# ZED-F9P_GNSS_FeatherWing.net
KiCad netlist of a schematic drawn in EAGLE
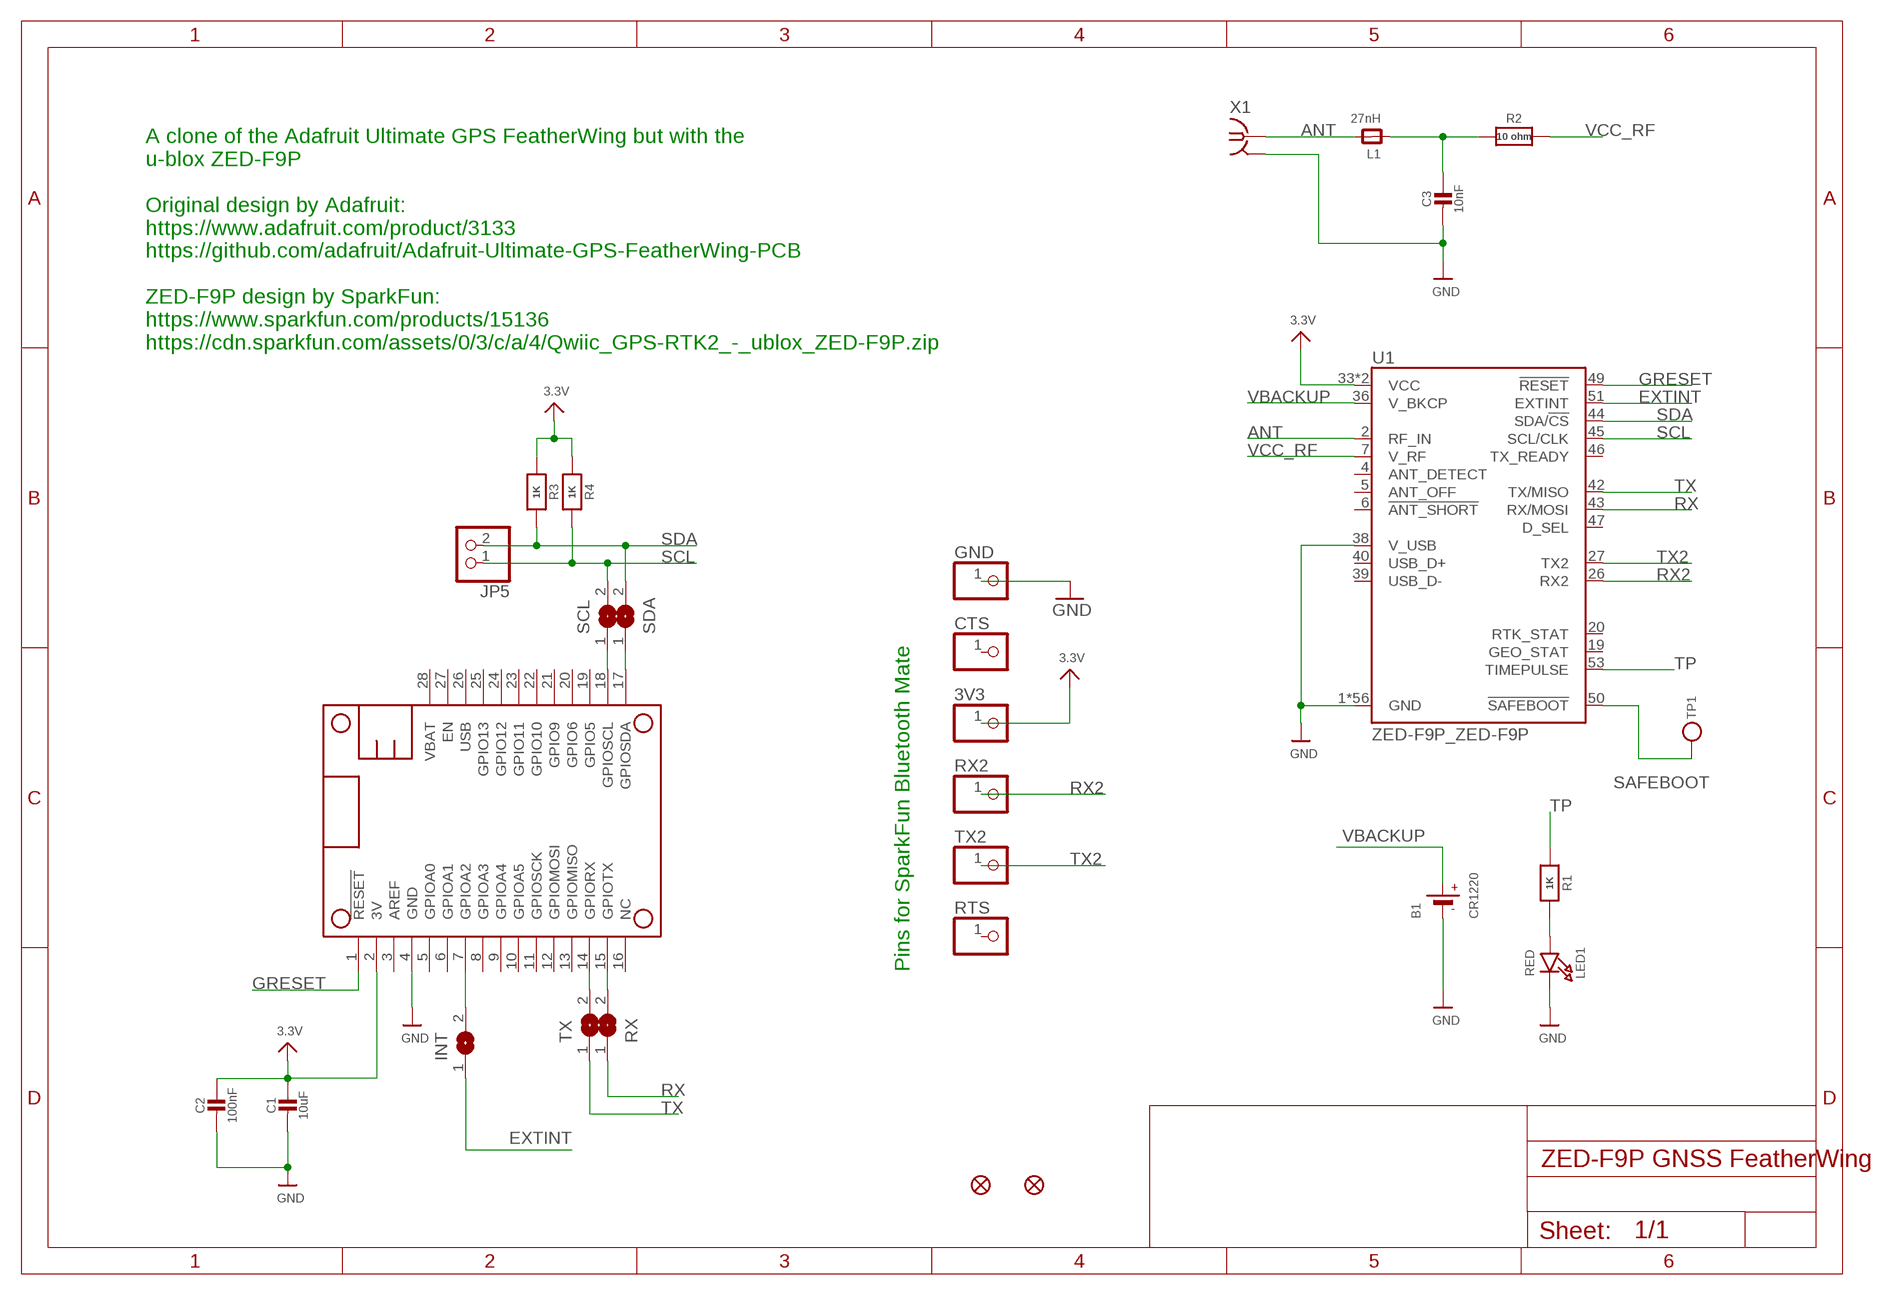
[diagram p0: schematic, sheet 1]

(export (version "E")
  (design (tool "Eeschema 10.0.6"))
  (components
    (comp (ref "3V3")
      (value "PINHD-1X1")
      (footprint "eagle-import:1X01")
      (libsource (lib "eagle-import") (part "PINHD-1X1"))
    )
    (comp (ref "B1")
      (value "CR1220")
      (footprint "eagle-import:CR1220-2")
      (libsource (lib "eagle-import") (part "BATTERYCR1220_2"))
    )
    (comp (ref "C1")
      (value "10uF")
      (footprint "eagle-import:0805-NO")
      (libsource (lib "eagle-import") (part "CAP_CERAMIC0805-NOOUTLINE"))
    )
    (comp (ref "C2")
      (value "100nF")
      (footprint "eagle-import:0805-NO")
      (libsource (lib "eagle-import") (part "CAP_CERAMIC0805-NOOUTLINE"))
    )
    (comp (ref "C3")
      (value "10nF")
      (footprint "eagle-import:0805-NO")
      (libsource (lib "eagle-import") (part "CAP_CERAMIC0805-NOOUTLINE"))
    )
    (comp (ref "CTS")
      (value "PINHD-1X1")
      (footprint "eagle-import:1X01")
      (libsource (lib "eagle-import") (part "PINHD-1X1"))
    )
    (comp (ref "FID1")
      (value "FIDUCIAL\"\"")
      (footprint "eagle-import:FIDUCIAL_1MM")
      (libsource (lib "eagle-import") (part "FIDUCIAL{dblquote}{dblquote}"))
    )
    (comp (ref "FID2")
      (value "FIDUCIAL\"\"")
      (footprint "eagle-import:FIDUCIAL_1MM")
      (libsource (lib "eagle-import") (part "FIDUCIAL{dblquote}{dblquote}"))
    )
    (comp (ref "GND")
      (value "PINHD-1X1")
      (footprint "eagle-import:1X01")
      (libsource (lib "eagle-import") (part "PINHD-1X1"))
    )
    (comp (ref "INT")
      (value "SOLDERJUMPERCLOSED")
      (footprint "eagle-import:SOLDERJUMPER_CLOSEDWIRE")
      (libsource (lib "eagle-import") (part "SOLDERJUMPERCLOSED"))
    )
    (comp (ref "JP5")
      (value "HEADER-1X2ROUND")
      (footprint "eagle-import:1X02_ROUND")
      (libsource (lib "eagle-import") (part "HEADER-1X2ROUND"))
    )
    (comp (ref "L1")
      (value "27nH")
      (footprint "eagle-import:0805-NO")
      (libsource (lib "eagle-import") (part "FERRITE-0805NO"))
    )
    (comp (ref "LED1")
      (value "RED")
      (footprint "eagle-import:CHIPLED_0805_NOOUTLINE")
      (libsource (lib "eagle-import") (part "LED0805_NOOUTLINE"))
    )
    (comp (ref "MS1")
      (value "MICROBUILDER_FEATHERWINGMICROBUILDER_FEATHERWING_HOLES")
      (footprint "eagle-import:MICROBUILDER_FEATHERWING_HOLES")
      (libsource (lib "eagle-import") (part "MICROBUILDER_FEATHERWINGMICROBUILDER_FEATHERWING_HOLES"))
    )
    (comp (ref "R1")
      (value "1K")
      (footprint "eagle-import:0603-NO")
      (libsource (lib "eagle-import") (part "RESISTOR_0603_NOOUT"))
    )
    (comp (ref "R2")
      (value "10 ohm")
      (footprint "eagle-import:0805-NO")
      (libsource (lib "eagle-import") (part "RESISTOR0805_NOOUTLINE"))
    )
    (comp (ref "R3")
      (value "1K")
      (footprint "eagle-import:0603-NO")
      (libsource (lib "eagle-import") (part "RESISTOR_0603_NOOUT"))
    )
    (comp (ref "R4")
      (value "1K")
      (footprint "eagle-import:0603-NO")
      (libsource (lib "eagle-import") (part "RESISTOR_0603_NOOUT"))
    )
    (comp (ref "RTS")
      (value "PINHD-1X1")
      (footprint "eagle-import:1X01")
      (libsource (lib "eagle-import") (part "PINHD-1X1"))
    )
    (comp (ref "RX")
      (value "SOLDERJUMPERCLOSED")
      (footprint "eagle-import:SOLDERJUMPER_CLOSEDWIRE")
      (libsource (lib "eagle-import") (part "SOLDERJUMPERCLOSED"))
    )
    (comp (ref "RX2")
      (value "PINHD-1X1")
      (footprint "eagle-import:1X01")
      (libsource (lib "eagle-import") (part "PINHD-1X1"))
    )
    (comp (ref "SCL")
      (value "SOLDERJUMPERCLOSED")
      (footprint "eagle-import:SOLDERJUMPER_CLOSEDWIRE")
      (libsource (lib "eagle-import") (part "SOLDERJUMPERCLOSED"))
    )
    (comp (ref "SDA")
      (value "SOLDERJUMPERCLOSED")
      (footprint "eagle-import:SOLDERJUMPER_CLOSEDWIRE")
      (libsource (lib "eagle-import") (part "SOLDERJUMPERCLOSED"))
    )
    (comp (ref "TP1")
      (value "TESTPOINTROUND1.5MM")
      (footprint "eagle-import:TESTPOINT_ROUND_1.5MM")
      (libsource (lib "eagle-import") (part "TESTPOINTROUND1.5MM"))
    )
    (comp (ref "TX")
      (value "SOLDERJUMPERCLOSED")
      (footprint "eagle-import:SOLDERJUMPER_CLOSEDWIRE")
      (libsource (lib "eagle-import") (part "SOLDERJUMPERCLOSED"))
    )
    (comp (ref "TX2")
      (value "PINHD-1X1")
      (footprint "eagle-import:1X01")
      (libsource (lib "eagle-import") (part "PINHD-1X1"))
    )
    (comp (ref "U1")
      (value "ZED-F9P_ZED-F9P")
      (footprint "eagle-import:ZED-F9P_ZED-F9P")
      (libsource (lib "eagle-import") (part "ZED-F9P_ZED-F9P"))
    )
    (comp (ref "X1")
      (value "SMA-142-0711-821/826")
      (footprint "eagle-import:J502-ND-142-0711-821_826")
      (fields (field (name "MF") "JOHNSON COMPONENTS") (field (name "MPN") "142-0711-821"))
      (libsource (lib "eagle-import") (part "SMA-142-0711-821/826"))
    )
  )
  (nets
    (net (code "1") (name "/ANT") (class "Default")
      (node (ref "L1") (pin "2") (pinfunction "P$2_2") (pintype "passive"))
      (node (ref "U1") (pin "2") (pinfunction "RF_IN_2") (pintype "bidirectional"))
      (node (ref "X1") (pin "1") (pinfunction "1_1") (pintype "passive"))
    )
    (net (code "2") (name "/EXTINT") (class "Default")
      (node (ref "INT") (pin "1") (pinfunction "1_1") (pintype "passive"))
      (node (ref "U1") (pin "51") (pinfunction "EXTINT_51") (pintype "bidirectional"))
    )
    (net (code "3") (name "/GRESET") (class "Default")
      (node (ref "MS1") (pin "1") (pinfunction "~{RESET}_1") (pintype "input"))
      (node (ref "U1") (pin "49") (pinfunction "~{RESET}_49") (pintype "bidirectional"))
    )
    (net (code "4") (name "/RX") (class "Default")
      (node (ref "RX") (pin "1") (pinfunction "1_1") (pintype "passive"))
      (node (ref "U1") (pin "43") (pinfunction "RX/MOSI_43") (pintype "bidirectional"))
    )
    (net (code "5") (name "/RX2") (class "Default")
      (node (ref "RX2") (pin "1") (pinfunction "1_1") (pintype "passive"))
      (node (ref "U1") (pin "26") (pinfunction "RX2_26") (pintype "bidirectional"))
    )
    (net (code "6") (name "/SAFEBOOT") (class "Default")
      (node (ref "TP1") (pin "P$1") (pinfunction "P$1_P$1") (pintype "bidirectional"))
      (node (ref "U1") (pin "50") (pinfunction "~{SAFEBOOT}_50") (pintype "bidirectional"))
    )
    (net (code "7") (name "/SCL") (class "Default")
      (node (ref "JP5") (pin "1") (pinfunction "1_1") (pintype "passive"))
      (node (ref "R4") (pin "2") (pinfunction "2_2") (pintype "passive"))
      (node (ref "SCL") (pin "2") (pinfunction "2_2") (pintype "passive"))
      (node (ref "U1") (pin "45") (pinfunction "SCL/CLK_45") (pintype "bidirectional"))
    )
    (net (code "8") (name "/SDA") (class "Default")
      (node (ref "JP5") (pin "2") (pinfunction "2_2") (pintype "passive"))
      (node (ref "R3") (pin "2") (pinfunction "2_2") (pintype "passive"))
      (node (ref "SDA") (pin "2") (pinfunction "2_2") (pintype "passive"))
      (node (ref "U1") (pin "44") (pinfunction "SDA/~{CS}_44") (pintype "bidirectional"))
    )
    (net (code "9") (name "/TP") (class "Default")
      (node (ref "R1") (pin "1") (pinfunction "1_1") (pintype "passive"))
      (node (ref "U1") (pin "53") (pinfunction "TIMEPULSE_53") (pintype "bidirectional"))
    )
    (net (code "10") (name "/TX") (class "Default")
      (node (ref "TX") (pin "1") (pinfunction "1_1") (pintype "passive"))
      (node (ref "U1") (pin "42") (pinfunction "TX/MISO_42") (pintype "bidirectional"))
    )
    (net (code "11") (name "/TX2") (class "Default")
      (node (ref "TX2") (pin "1") (pinfunction "1_1") (pintype "passive"))
      (node (ref "U1") (pin "27") (pinfunction "TX2_27") (pintype "bidirectional"))
    )
    (net (code "12") (name "/USB") (class "Default")
      (node (ref "MS1") (pin "26") (pinfunction "USB_26") (pintype "power_in"))
    )
    (net (code "13") (name "/VBACKUP") (class "Default")
      (node (ref "B1") (pin "+") (pinfunction "+_+") (pintype "passive"))
      (node (ref "U1") (pin "36") (pinfunction "V_BKCP_36") (pintype "bidirectional"))
    )
    (net (code "14") (name "/VBAT") (class "Default")
      (node (ref "MS1") (pin "28") (pinfunction "VBAT_28") (pintype "power_in"))
    )
    (net (code "15") (name "/VCC_RF") (class "Default")
      (node (ref "R2") (pin "2") (pinfunction "2_2") (pintype "passive"))
      (node (ref "U1") (pin "7") (pinfunction "V_RF_7") (pintype "bidirectional"))
    )
    (net (code "16") (name "3.3V") (class "Default")
      (node (ref "3V3") (pin "1") (pinfunction "1_1") (pintype "passive"))
      (node (ref "C1") (pin "1") (pinfunction "1_1") (pintype "passive"))
      (node (ref "C2") (pin "1") (pinfunction "1_1") (pintype "passive"))
      (node (ref "MS1") (pin "2") (pinfunction "3V_2") (pintype "power_in"))
      (node (ref "R3") (pin "1") (pinfunction "1_1") (pintype "passive"))
      (node (ref "R4") (pin "1") (pinfunction "1_1") (pintype "passive"))
      (node (ref "U1") (pin "33") (pinfunction "VCC_33") (pintype "bidirectional"))
      (node (ref "U1") (pin "34") (pinfunction "VCC_34") (pintype "bidirectional"))
    )
    (net (code "17") (name "GND") (class "Default")
      (node (ref "B1") (pin "-") (pinfunction "-_-") (pintype "passive"))
      (node (ref "C1") (pin "2") (pinfunction "2_2") (pintype "passive"))
      (node (ref "C2") (pin "2") (pinfunction "2_2") (pintype "passive"))
      (node (ref "C3") (pin "2") (pinfunction "2_2") (pintype "passive"))
      (node (ref "GND") (pin "1") (pinfunction "1_1") (pintype "passive"))
      (node (ref "LED1") (pin "C") (pinfunction "C_C") (pintype "passive"))
      (node (ref "MS1") (pin "4") (pinfunction "GND_4") (pintype "power_in"))
      (node (ref "U1") (pin "1") (pinfunction "GND_1") (pintype "bidirectional"))
      (node (ref "U1") (pin "100") (pinfunction "GND_100") (pintype "bidirectional"))
      (node (ref "U1") (pin "101") (pinfunction "GND_101") (pintype "bidirectional"))
      (node (ref "U1") (pin "102") (pinfunction "GND_102") (pintype "bidirectional"))
      (node (ref "U1") (pin "12") (pinfunction "GND_12") (pintype "bidirectional"))
      (node (ref "U1") (pin "14") (pinfunction "GND_14") (pintype "bidirectional"))
      (node (ref "U1") (pin "3") (pinfunction "GND_3") (pintype "bidirectional"))
      (node (ref "U1") (pin "32") (pinfunction "GND_32") (pintype "bidirectional"))
      (node (ref "U1") (pin "37") (pinfunction "GND_37") (pintype "bidirectional"))
      (node (ref "U1") (pin "38") (pinfunction "V_USB_38") (pintype "bidirectional"))
      (node (ref "U1") (pin "41") (pinfunction "GND_41") (pintype "bidirectional"))
      (node (ref "U1") (pin "48") (pinfunction "GND_48") (pintype "bidirectional"))
      (node (ref "U1") (pin "55") (pinfunction "GND_55") (pintype "bidirectional"))
      (node (ref "U1") (pin "56") (pinfunction "GND_56") (pintype "bidirectional"))
      (node (ref "U1") (pin "57") (pinfunction "GND_57") (pintype "bidirectional"))
      (node (ref "U1") (pin "58") (pinfunction "GND_58") (pintype "bidirectional"))
      (node (ref "U1") (pin "59") (pinfunction "GND_59") (pintype "bidirectional"))
      (node (ref "U1") (pin "60") (pinfunction "GND_60") (pintype "bidirectional"))
      (node (ref "U1") (pin "61") (pinfunction "GND_61") (pintype "bidirectional"))
      (node (ref "U1") (pin "62") (pinfunction "GND_62") (pintype "bidirectional"))
      (node (ref "U1") (pin "63") (pinfunction "GND_63") (pintype "bidirectional"))
      (node (ref "U1") (pin "64") (pinfunction "GND_64") (pintype "bidirectional"))
      (node (ref "U1") (pin "65") (pinfunction "GND_65") (pintype "bidirectional"))
      (node (ref "U1") (pin "66") (pinfunction "GND_66") (pintype "bidirectional"))
      (node (ref "U1") (pin "67") (pinfunction "GND_67") (pintype "bidirectional"))
      (node (ref "U1") (pin "68") (pinfunction "GND_68") (pintype "bidirectional"))
      (node (ref "U1") (pin "69") (pinfunction "GND_69") (pintype "bidirectional"))
      (node (ref "U1") (pin "70") (pinfunction "GND_70") (pintype "bidirectional"))
      (node (ref "U1") (pin "71") (pinfunction "GND_71") (pintype "bidirectional"))
      (node (ref "U1") (pin "72") (pinfunction "GND_72") (pintype "bidirectional"))
      (node (ref "U1") (pin "73") (pinfunction "GND_73") (pintype "bidirectional"))
      (node (ref "U1") (pin "74") (pinfunction "GND_74") (pintype "bidirectional"))
      (node (ref "U1") (pin "75") (pinfunction "GND_75") (pintype "bidirectional"))
      (node (ref "U1") (pin "76") (pinfunction "GND_76") (pintype "bidirectional"))
      (node (ref "U1") (pin "77") (pinfunction "GND_77") (pintype "bidirectional"))
      (node (ref "U1") (pin "78") (pinfunction "GND_78") (pintype "bidirectional"))
      (node (ref "U1") (pin "79") (pinfunction "GND_79") (pintype "bidirectional"))
      (node (ref "U1") (pin "80") (pinfunction "GND_80") (pintype "bidirectional"))
      (node (ref "U1") (pin "81") (pinfunction "GND_81") (pintype "bidirectional"))
      (node (ref "U1") (pin "82") (pinfunction "GND_82") (pintype "bidirectional"))
      (node (ref "U1") (pin "83") (pinfunction "GND_83") (pintype "bidirectional"))
      (node (ref "U1") (pin "84") (pinfunction "GND_84") (pintype "bidirectional"))
      (node (ref "U1") (pin "85") (pinfunction "GND_85") (pintype "bidirectional"))
      (node (ref "U1") (pin "86") (pinfunction "GND_86") (pintype "bidirectional"))
      (node (ref "U1") (pin "87") (pinfunction "GND_87") (pintype "bidirectional"))
      (node (ref "U1") (pin "88") (pinfunction "GND_88") (pintype "bidirectional"))
      (node (ref "U1") (pin "89") (pinfunction "GND_89") (pintype "bidirectional"))
      (node (ref "U1") (pin "90") (pinfunction "GND_90") (pintype "bidirectional"))
      (node (ref "U1") (pin "91") (pinfunction "GND_91") (pintype "bidirectional"))
      (node (ref "U1") (pin "92") (pinfunction "GND_92") (pintype "bidirectional"))
      (node (ref "U1") (pin "93") (pinfunction "GND_93") (pintype "bidirectional"))
      (node (ref "U1") (pin "94") (pinfunction "GND_94") (pintype "bidirectional"))
      (node (ref "U1") (pin "95") (pinfunction "GND_95") (pintype "bidirectional"))
      (node (ref "U1") (pin "96") (pinfunction "GND_96") (pintype "bidirectional"))
      (node (ref "U1") (pin "97") (pinfunction "GND_97") (pintype "bidirectional"))
      (node (ref "U1") (pin "98") (pinfunction "GND_98") (pintype "bidirectional"))
      (node (ref "U1") (pin "99") (pinfunction "GND_99") (pintype "bidirectional"))
      (node (ref "X1") (pin "G@1") (pinfunction "2_G@1") (pintype "passive"))
      (node (ref "X1") (pin "G@2") (pinfunction "2_G@2") (pintype "passive"))
      (node (ref "X1") (pin "G@3") (pinfunction "2_G@3") (pintype "passive"))
      (node (ref "X1") (pin "G@4") (pinfunction "2_G@4") (pintype "passive"))
    )
    (net (code "18") (name "Net-(L1-P$1)") (class "Default")
      (node (ref "C3") (pin "1") (pinfunction "1_1") (pintype "passive"))
      (node (ref "L1") (pin "1") (pinfunction "P$1_1") (pintype "passive"))
      (node (ref "R2") (pin "1") (pinfunction "1_1") (pintype "passive"))
    )
    (net (code "19") (name "Net-(LED1-PadA)") (class "Default")
      (node (ref "LED1") (pin "A") (pinfunction "A_A") (pintype "passive"))
      (node (ref "R1") (pin "2") (pinfunction "2_2") (pintype "passive"))
    )
    (net (code "20") (name "Net-(MS1-GPIOA2)") (class "Default")
      (node (ref "INT") (pin "2") (pinfunction "2_2") (pintype "passive"))
      (node (ref "MS1") (pin "7") (pinfunction "GPIOA2_7") (pintype "bidirectional"))
    )
    (net (code "21") (name "Net-(MS1-GPIORX)") (class "Default")
      (node (ref "MS1") (pin "14") (pinfunction "GPIORX_14") (pintype "bidirectional"))
      (node (ref "TX") (pin "2") (pinfunction "2_2") (pintype "passive"))
    )
    (net (code "22") (name "Net-(MS1-GPIOSCL)") (class "Default")
      (node (ref "MS1") (pin "18") (pinfunction "GPIOSCL_18") (pintype "bidirectional"))
      (node (ref "SCL") (pin "1") (pinfunction "1_1") (pintype "passive"))
    )
    (net (code "23") (name "Net-(MS1-GPIOSDA)") (class "Default")
      (node (ref "MS1") (pin "17") (pinfunction "GPIOSDA_17") (pintype "bidirectional"))
      (node (ref "SDA") (pin "1") (pinfunction "1_1") (pintype "passive"))
    )
    (net (code "24") (name "Net-(MS1-GPIOTX)") (class "Default")
      (node (ref "MS1") (pin "15") (pinfunction "GPIOTX_15") (pintype "bidirectional"))
      (node (ref "RX") (pin "2") (pinfunction "2_2") (pintype "passive"))
    )
    (net (code "25") (name "unconnected-(CTS-Pad1)") (class "Default")
      (node (ref "CTS") (pin "1") (pinfunction "1_1") (pintype "passive"))
    )
    (net (code "26") (name "unconnected-(MS1-AREF-Pad3)") (class "Default")
      (node (ref "MS1") (pin "3") (pinfunction "AREF_3") (pintype "passive"))
    )
    (net (code "27") (name "unconnected-(MS1-EN-Pad27)") (class "Default")
      (node (ref "MS1") (pin "27") (pinfunction "EN_27") (pintype "passive"))
    )
    (net (code "28") (name "unconnected-(MS1-GPIO5-Pad19)") (class "Default")
      (node (ref "MS1") (pin "19") (pinfunction "GPIO5_19") (pintype "bidirectional"))
    )
    (net (code "29") (name "unconnected-(MS1-GPIO6-Pad20)") (class "Default")
      (node (ref "MS1") (pin "20") (pinfunction "GPIO6_20") (pintype "bidirectional"))
    )
    (net (code "30") (name "unconnected-(MS1-GPIO9-Pad21)") (class "Default")
      (node (ref "MS1") (pin "21") (pinfunction "GPIO9_21") (pintype "bidirectional"))
    )
    (net (code "31") (name "unconnected-(MS1-GPIO10-Pad22)") (class "Default")
      (node (ref "MS1") (pin "22") (pinfunction "GPIO10_22") (pintype "bidirectional"))
    )
    (net (code "32") (name "unconnected-(MS1-GPIO11-Pad23)") (class "Default")
      (node (ref "MS1") (pin "23") (pinfunction "GPIO11_23") (pintype "bidirectional"))
    )
    (net (code "33") (name "unconnected-(MS1-GPIO12-Pad24)") (class "Default")
      (node (ref "MS1") (pin "24") (pinfunction "GPIO12_24") (pintype "bidirectional"))
    )
    (net (code "34") (name "unconnected-(MS1-GPIO13-Pad25)") (class "Default")
      (node (ref "MS1") (pin "25") (pinfunction "GPIO13_25") (pintype "bidirectional"))
    )
    (net (code "35") (name "unconnected-(MS1-GPIOA0-Pad5)") (class "Default")
      (node (ref "MS1") (pin "5") (pinfunction "GPIOA0_5") (pintype "bidirectional"))
    )
    (net (code "36") (name "unconnected-(MS1-GPIOA1-Pad6)") (class "Default")
      (node (ref "MS1") (pin "6") (pinfunction "GPIOA1_6") (pintype "bidirectional"))
    )
    (net (code "37") (name "unconnected-(MS1-GPIOA3-Pad8)") (class "Default")
      (node (ref "MS1") (pin "8") (pinfunction "GPIOA3_8") (pintype "bidirectional"))
    )
    (net (code "38") (name "unconnected-(MS1-GPIOA4-Pad9)") (class "Default")
      (node (ref "MS1") (pin "9") (pinfunction "GPIOA4_9") (pintype "bidirectional"))
    )
    (net (code "39") (name "unconnected-(MS1-GPIOA5-Pad10)") (class "Default")
      (node (ref "MS1") (pin "10") (pinfunction "GPIOA5_10") (pintype "bidirectional"))
    )
    (net (code "40") (name "unconnected-(MS1-GPIOMISO-Pad13)") (class "Default")
      (node (ref "MS1") (pin "13") (pinfunction "GPIOMISO_13") (pintype "bidirectional"))
    )
    (net (code "41") (name "unconnected-(MS1-GPIOMOSI-Pad12)") (class "Default")
      (node (ref "MS1") (pin "12") (pinfunction "GPIOMOSI_12") (pintype "bidirectional"))
    )
    (net (code "42") (name "unconnected-(MS1-GPIOSCK-Pad11)") (class "Default")
      (node (ref "MS1") (pin "11") (pinfunction "GPIOSCK_11") (pintype "bidirectional"))
    )
    (net (code "43") (name "unconnected-(MS1-NC-Pad16)") (class "Default")
      (node (ref "MS1") (pin "16") (pinfunction "NC_16") (pintype "passive"))
    )
    (net (code "44") (name "unconnected-(RTS-Pad1)") (class "Default")
      (node (ref "RTS") (pin "1") (pinfunction "1_1") (pintype "passive"))
    )
    (net (code "45") (name "unconnected-(U1-ANT_DETECT-Pad4)") (class "Default")
      (node (ref "U1") (pin "4") (pinfunction "ANT_DETECT_4") (pintype "bidirectional"))
    )
    (net (code "46") (name "unconnected-(U1-ANT_OFF-Pad5)") (class "Default")
      (node (ref "U1") (pin "5") (pinfunction "ANT_OFF_5") (pintype "bidirectional"))
    )
    (net (code "47") (name "unconnected-(U1-D_SEL-Pad47)") (class "Default")
      (node (ref "U1") (pin "47") (pinfunction "D_SEL_47") (pintype "bidirectional"))
    )
    (net (code "48") (name "unconnected-(U1-GEO_STAT-Pad19)") (class "Default")
      (node (ref "U1") (pin "19") (pinfunction "GEO_STAT_19") (pintype "bidirectional"))
    )
    (net (code "49") (name "unconnected-(U1-RTK_STAT-Pad20)") (class "Default")
      (node (ref "U1") (pin "20") (pinfunction "RTK_STAT_20") (pintype "bidirectional"))
    )
    (net (code "50") (name "unconnected-(U1-TX_READY-Pad46)") (class "Default")
      (node (ref "U1") (pin "46") (pinfunction "TX_READY_46") (pintype "bidirectional"))
    )
    (net (code "51") (name "unconnected-(U1-USB_D+-Pad40)") (class "Default")
      (node (ref "U1") (pin "40") (pinfunction "USB_D+_40") (pintype "bidirectional"))
    )
    (net (code "52") (name "unconnected-(U1-USB_D--Pad39)") (class "Default")
      (node (ref "U1") (pin "39") (pinfunction "USB_D-_39") (pintype "bidirectional"))
    )
    (net (code "53") (name "unconnected-(U1-~{ANT_SHORT}-Pad6)") (class "Default")
      (node (ref "U1") (pin "6") (pinfunction "~{ANT_SHORT}_6") (pintype "bidirectional"))
    )
  )
)
